# vca_core.net
KiCad netlist of a schematic drawn in Altium Designer
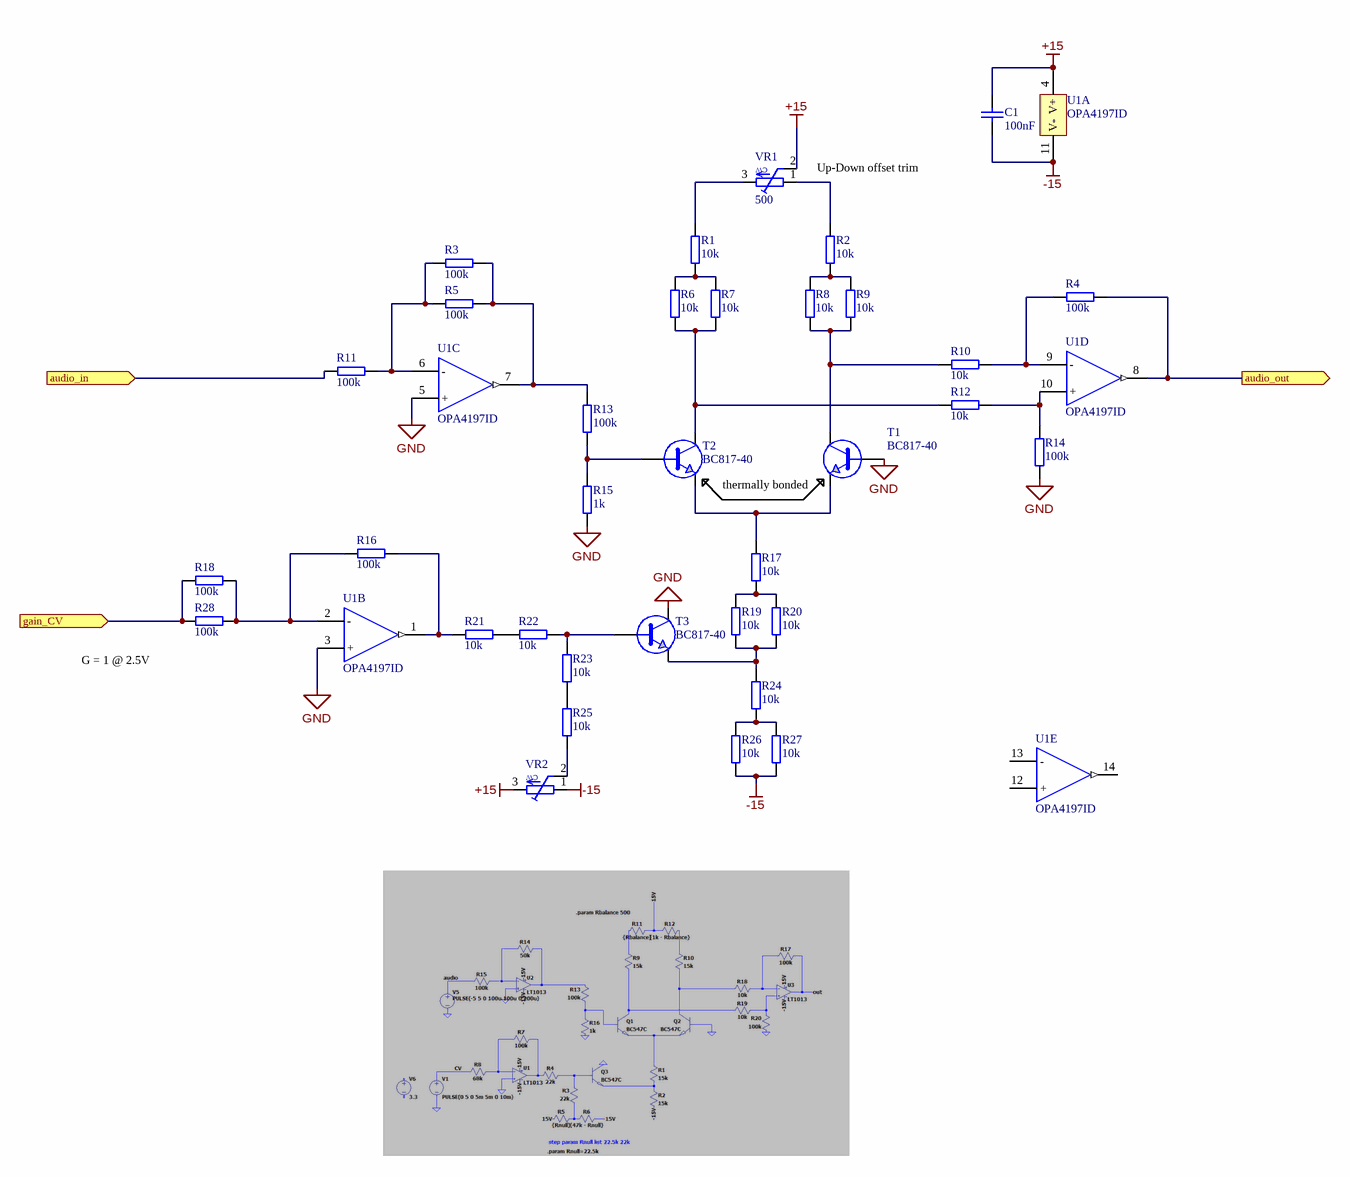
[diagram p0: vca_core.SchDoc]

(export (version "E")
  (design (tool "Eeschema 10.0.6"))
  (components
    (comp (ref "C1")
      (value "100nF")
      (footprint "WCAP-CSGP_0603_L1.6W0.8H0.8_Reflow")
      (description "WCAP-CSGP Multilayer Ceramic Chip Capacitor, General Purpose, size 0603, X7R, 100nF, 50V")
      (fields
        (field (name "MANUFACTURER") "Wurth Elektronik")
        (field (name "MANUFACTURER PART NUMBER") "885012206095")
      )
      (libsource (lib "Altium_WCAP-CSGP (rev22a)") (part "885012206095"))
    )
    (comp (ref "R1")
      (value "10k")
      (footprint "RESC1608X06N(SMR0603)")
      (description "Thick Film resistor, 0603 Size, universal value, 0.1 W")
      (libsource (lib "Kubikova integrovana knihovna ") (part "R 0603 universal"))
    )
    (comp (ref "R2")
      (value "10k")
      (footprint "RESC1608X06N(SMR0603)")
      (description "Thick Film resistor, 0603 Size, universal value, 0.1 W")
      (libsource (lib "Kubikova integrovana knihovna ") (part "R 0603 universal"))
    )
    (comp (ref "R3")
      (value "100k")
      (footprint "RESC1608X06N(SMR0603)")
      (description "Thick Film resistor, 0603 Size, universal value, 0.1 W")
      (libsource (lib "Kubikova integrovana knihovna ") (part "R 0603 universal"))
    )
    (comp (ref "R4")
      (value "100k")
      (footprint "RESC1608X06N(SMR0603)")
      (description "Thick Film resistor, 0603 Size, universal value, 0.1 W")
      (libsource (lib "Kubikova integrovana knihovna ") (part "R 0603 universal"))
    )
    (comp (ref "R5")
      (value "100k")
      (footprint "RESC1608X06N(SMR0603)")
      (description "Thick Film resistor, 0603 Size, universal value, 0.1 W")
      (libsource (lib "Kubikova integrovana knihovna ") (part "R 0603 universal"))
    )
    (comp (ref "R6")
      (value "10k")
      (footprint "RESC1608X06N(SMR0603)")
      (description "Thick Film resistor, 0603 Size, universal value, 0.1 W")
      (libsource (lib "Kubikova integrovana knihovna ") (part "R 0603 universal"))
    )
    (comp (ref "R7")
      (value "10k")
      (footprint "RESC1608X06N(SMR0603)")
      (description "Thick Film resistor, 0603 Size, universal value, 0.1 W")
      (libsource (lib "Kubikova integrovana knihovna ") (part "R 0603 universal"))
    )
    (comp (ref "R8")
      (value "10k")
      (footprint "RESC1608X06N(SMR0603)")
      (description "Thick Film resistor, 0603 Size, universal value, 0.1 W")
      (libsource (lib "Kubikova integrovana knihovna ") (part "R 0603 universal"))
    )
    (comp (ref "R9")
      (value "10k")
      (footprint "RESC1608X06N(SMR0603)")
      (description "Thick Film resistor, 0603 Size, universal value, 0.1 W")
      (libsource (lib "Kubikova integrovana knihovna ") (part "R 0603 universal"))
    )
    (comp (ref "R10")
      (value "10k")
      (footprint "RESC1608X06N(SMR0603)")
      (description "Thick Film resistor, 0603 Size, universal value, 0.1 W")
      (libsource (lib "Kubikova integrovana knihovna ") (part "R 0603 universal"))
    )
    (comp (ref "R11")
      (value "100k")
      (footprint "RESC1608X06N(SMR0603)")
      (description "Thick Film resistor, 0603 Size, universal value, 0.1 W")
      (libsource (lib "Kubikova integrovana knihovna ") (part "R 0603 universal"))
    )
    (comp (ref "R12")
      (value "10k")
      (footprint "RESC1608X06N(SMR0603)")
      (description "Thick Film resistor, 0603 Size, universal value, 0.1 W")
      (libsource (lib "Kubikova integrovana knihovna ") (part "R 0603 universal"))
    )
    (comp (ref "R13")
      (value "100k")
      (footprint "RESC1608X06N(SMR0603)")
      (description "Thick Film resistor, 0603 Size, universal value, 0.1 W")
      (libsource (lib "Kubikova integrovana knihovna ") (part "R 0603 universal"))
    )
    (comp (ref "R14")
      (value "100k")
      (footprint "RESC1608X06N(SMR0603)")
      (description "Thick Film resistor, 0603 Size, universal value, 0.1 W")
      (libsource (lib "Kubikova integrovana knihovna ") (part "R 0603 universal"))
    )
    (comp (ref "R15")
      (value "1k")
      (footprint "RESC1608X06N(SMR0603)")
      (description "Thick Film resistor, 0603 Size, universal value, 0.1 W")
      (libsource (lib "Kubikova integrovana knihovna ") (part "R 0603 universal"))
    )
    (comp (ref "R16")
      (value "100k")
      (footprint "RESC1608X06N(SMR0603)")
      (description "Thick Film resistor, 0603 Size, universal value, 0.1 W")
      (libsource (lib "Kubikova integrovana knihovna ") (part "R 0603 universal"))
    )
    (comp (ref "R17")
      (value "10k")
      (footprint "RESC1608X06N(SMR0603)")
      (description "Thick Film resistor, 0603 Size, universal value, 0.1 W")
      (libsource (lib "Kubikova integrovana knihovna ") (part "R 0603 universal"))
    )
    (comp (ref "R18")
      (value "100k")
      (footprint "RESC1608X06N(SMR0603)")
      (description "Thick Film resistor, 0603 Size, universal value, 0.1 W")
      (libsource (lib "Kubikova integrovana knihovna ") (part "R 0603 universal"))
    )
    (comp (ref "R19")
      (value "10k")
      (footprint "RESC1608X06N(SMR0603)")
      (description "Thick Film resistor, 0603 Size, universal value, 0.1 W")
      (libsource (lib "Kubikova integrovana knihovna ") (part "R 0603 universal"))
    )
    (comp (ref "R20")
      (value "10k")
      (footprint "RESC1608X06N(SMR0603)")
      (description "Thick Film resistor, 0603 Size, universal value, 0.1 W")
      (libsource (lib "Kubikova integrovana knihovna ") (part "R 0603 universal"))
    )
    (comp (ref "R21")
      (value "10k")
      (footprint "RESC1608X06N(SMR0603)")
      (description "Thick Film resistor, 0603 Size, universal value, 0.1 W")
      (libsource (lib "Kubikova integrovana knihovna ") (part "R 0603 universal"))
    )
    (comp (ref "R22")
      (value "10k")
      (footprint "RESC1608X06N(SMR0603)")
      (description "Thick Film resistor, 0603 Size, universal value, 0.1 W")
      (libsource (lib "Kubikova integrovana knihovna ") (part "R 0603 universal"))
    )
    (comp (ref "R23")
      (value "10k")
      (footprint "RESC1608X06N(SMR0603)")
      (description "Thick Film resistor, 0603 Size, universal value, 0.1 W")
      (libsource (lib "Kubikova integrovana knihovna ") (part "R 0603 universal"))
    )
    (comp (ref "R24")
      (value "10k")
      (footprint "RESC1608X06N(SMR0603)")
      (description "Thick Film resistor, 0603 Size, universal value, 0.1 W")
      (libsource (lib "Kubikova integrovana knihovna ") (part "R 0603 universal"))
    )
    (comp (ref "R25")
      (value "10k")
      (footprint "RESC1608X06N(SMR0603)")
      (description "Thick Film resistor, 0603 Size, universal value, 0.1 W")
      (libsource (lib "Kubikova integrovana knihovna ") (part "R 0603 universal"))
    )
    (comp (ref "R26")
      (value "10k")
      (footprint "RESC1608X06N(SMR0603)")
      (description "Thick Film resistor, 0603 Size, universal value, 0.1 W")
      (libsource (lib "Kubikova integrovana knihovna ") (part "R 0603 universal"))
    )
    (comp (ref "R27")
      (value "10k")
      (footprint "RESC1608X06N(SMR0603)")
      (description "Thick Film resistor, 0603 Size, universal value, 0.1 W")
      (libsource (lib "Kubikova integrovana knihovna ") (part "R 0603 universal"))
    )
    (comp (ref "R28")
      (value "100k")
      (footprint "RESC1608X06N(SMR0603)")
      (description "Thick Film resistor, 0603 Size, universal value, 0.1 W")
      (libsource (lib "Kubikova integrovana knihovna ") (part "R 0603 universal"))
    )
    (comp (ref "T1")
      (value "BC817-40")
      (footprint "SOT95P230X110-3N(SOT23)")
      (description "SSw; NPN; ??Ohm; 45V; 0.5A; 1x;")
      (libsource (lib "altium_sql") (part "NPN_BEC"))
    )
    (comp (ref "T2")
      (value "BC817-40")
      (footprint "SOT95P230X110-3N(SOT23)")
      (description "SSw; NPN; ??Ohm; 45V; 0.5A; 1x;")
      (libsource (lib "altium_sql") (part "NPN_BEC"))
    )
    (comp (ref "T3")
      (value "BC817-40")
      (footprint "SOT95P230X110-3N(SOT23)")
      (description "SSw; NPN; ??Ohm; 45V; 0.5A; 1x;")
      (libsource (lib "altium_sql") (part "NPN_BEC"))
    )
    (comp (ref "U1")
      (value "OPA4197ID")
      (footprint "SOIC127P600X175-14N(SO-14)")
      (description "IC; Opamp; 4.5V; 36V; 4x;")
      (fields (field (name "MANUFACTURER") "Texas Instruments: OPA4197IDR"))
      (libsource (lib "altium_sql") (part "OP_AMP_QUAD_1"))
    )
    (comp (ref "VR1")
      (value "500")
      (footprint "64W")
      (description "093 - 3/8\" Square (10 mm) Multi-Turn Cermet Trimmer")
      (libsource (lib "Kubikova integrovana knihovna ") (part "Trimmer universal 3/8 (10mm)"))
    )
    (comp (ref "VR2")
      (value "~")
      (footprint "64W")
      (description "093 - 3/8\" Square (10 mm) Multi-Turn Cermet Trimmer")
      (libsource (lib "Kubikova integrovana knihovna ") (part "Trimmer universal 3/8 (10mm)"))
    )
  )
  (nets
    (net (code "1") (name "+15") (class "Default")
      (node (ref "C1") (pin "2") (pinfunction "2_2") (pintype "passive"))
      (node (ref "U1") (pin "4") (pinfunction "V+_4") (pintype "power_in"))
      (node (ref "VR1") (pin "2") (pinfunction "2_2") (pintype "passive"))
      (node (ref "VR2") (pin "3") (pinfunction "3_3") (pintype "passive"))
    )
    (net (code "2") (name "-15") (class "Default")
      (node (ref "C1") (pin "1") (pinfunction "1_1") (pintype "passive"))
      (node (ref "R26") (pin "2") (pinfunction "2_2") (pintype "passive"))
      (node (ref "R27") (pin "2") (pinfunction "2_2") (pintype "passive"))
      (node (ref "U1") (pin "11") (pinfunction "V-_11") (pintype "power_in"))
      (node (ref "VR2") (pin "1") (pinfunction "1_1") (pintype "passive"))
    )
    (net (code "3") (name "/audio_in") (class "Default")
      (node (ref "R11") (pin "1") (pinfunction "1_1") (pintype "passive"))
    )
    (net (code "4") (name "/audio_out") (class "Default")
      (node (ref "R4") (pin "1") (pinfunction "1_1") (pintype "passive"))
      (node (ref "U1") (pin "8") (pinfunction "OUT3_8") (pintype "output"))
    )
    (net (code "5") (name "/gain_CV") (class "Default")
      (node (ref "R18") (pin "2") (pinfunction "2_2") (pintype "passive"))
      (node (ref "R28") (pin "2") (pinfunction "2_2") (pintype "passive"))
    )
    (net (code "6") (name "GND") (class "Default")
      (node (ref "R14") (pin "1") (pinfunction "1_1") (pintype "passive"))
      (node (ref "R15") (pin "2") (pinfunction "2_2") (pintype "passive"))
      (node (ref "T1") (pin "1") (pinfunction "B_1") (pintype "passive"))
      (node (ref "T3") (pin "3") (pinfunction "C_3") (pintype "passive"))
      (node (ref "U1") (pin "3") (pinfunction "+_3") (pintype "passive"))
      (node (ref "U1") (pin "5") (pinfunction "+_5") (pintype "passive"))
    )
    (net (code "7") (name "Net-(R1-Pad1)") (class "Default")
      (node (ref "R1") (pin "1") (pinfunction "1_1") (pintype "passive"))
      (node (ref "VR1") (pin "3") (pinfunction "3_3") (pintype "passive"))
    )
    (net (code "8") (name "Net-(R1-Pad2)") (class "Default")
      (node (ref "R1") (pin "2") (pinfunction "2_2") (pintype "passive"))
      (node (ref "R6") (pin "1") (pinfunction "1_1") (pintype "passive"))
      (node (ref "R7") (pin "1") (pinfunction "1_1") (pintype "passive"))
    )
    (net (code "9") (name "Net-(R2-Pad1)") (class "Default")
      (node (ref "R2") (pin "1") (pinfunction "1_1") (pintype "passive"))
      (node (ref "VR1") (pin "1") (pinfunction "1_1") (pintype "passive"))
    )
    (net (code "10") (name "Net-(R2-Pad2)") (class "Default")
      (node (ref "R2") (pin "2") (pinfunction "2_2") (pintype "passive"))
      (node (ref "R8") (pin "1") (pinfunction "1_1") (pintype "passive"))
      (node (ref "R9") (pin "1") (pinfunction "1_1") (pintype "passive"))
    )
    (net (code "11") (name "Net-(R17-Pad2)") (class "Default")
      (node (ref "R17") (pin "2") (pinfunction "2_2") (pintype "passive"))
      (node (ref "R19") (pin "1") (pinfunction "1_1") (pintype "passive"))
      (node (ref "R20") (pin "1") (pinfunction "1_1") (pintype "passive"))
    )
    (net (code "12") (name "Net-(R21-Pad2)") (class "Default")
      (node (ref "R21") (pin "2") (pinfunction "2_2") (pintype "passive"))
      (node (ref "R22") (pin "1") (pinfunction "1_1") (pintype "passive"))
    )
    (net (code "13") (name "Net-(R23-Pad2)") (class "Default")
      (node (ref "R23") (pin "2") (pinfunction "2_2") (pintype "passive"))
      (node (ref "R25") (pin "1") (pinfunction "1_1") (pintype "passive"))
    )
    (net (code "14") (name "Net-(R24-Pad2)") (class "Default")
      (node (ref "R24") (pin "2") (pinfunction "2_2") (pintype "passive"))
      (node (ref "R26") (pin "1") (pinfunction "1_1") (pintype "passive"))
      (node (ref "R27") (pin "1") (pinfunction "1_1") (pintype "passive"))
    )
    (net (code "15") (name "Net-(R25-Pad2)") (class "Default")
      (node (ref "R25") (pin "2") (pinfunction "2_2") (pintype "passive"))
      (node (ref "VR2") (pin "2") (pinfunction "2_2") (pintype "passive"))
    )
    (net (code "16") (name "Net-(T1-C)") (class "Default")
      (node (ref "R10") (pin "2") (pinfunction "2_2") (pintype "passive"))
      (node (ref "R8") (pin "2") (pinfunction "2_2") (pintype "passive"))
      (node (ref "R9") (pin "2") (pinfunction "2_2") (pintype "passive"))
      (node (ref "T1") (pin "3") (pinfunction "C_3") (pintype "passive"))
    )
    (net (code "17") (name "Net-(T1-E)") (class "Default")
      (node (ref "R17") (pin "1") (pinfunction "1_1") (pintype "passive"))
      (node (ref "T1") (pin "2") (pinfunction "E_2") (pintype "passive"))
      (node (ref "T2") (pin "2") (pinfunction "E_2") (pintype "passive"))
    )
    (net (code "18") (name "Net-(T2-B)") (class "Default")
      (node (ref "R13") (pin "2") (pinfunction "2_2") (pintype "passive"))
      (node (ref "R15") (pin "1") (pinfunction "1_1") (pintype "passive"))
      (node (ref "T2") (pin "1") (pinfunction "B_1") (pintype "passive"))
    )
    (net (code "19") (name "Net-(T2-C)") (class "Default")
      (node (ref "R12") (pin "2") (pinfunction "2_2") (pintype "passive"))
      (node (ref "R6") (pin "2") (pinfunction "2_2") (pintype "passive"))
      (node (ref "R7") (pin "2") (pinfunction "2_2") (pintype "passive"))
      (node (ref "T2") (pin "3") (pinfunction "C_3") (pintype "passive"))
    )
    (net (code "20") (name "Net-(T3-B)") (class "Default")
      (node (ref "R22") (pin "2") (pinfunction "2_2") (pintype "passive"))
      (node (ref "R23") (pin "1") (pinfunction "1_1") (pintype "passive"))
      (node (ref "T3") (pin "1") (pinfunction "B_1") (pintype "passive"))
    )
    (net (code "21") (name "Net-(T3-E)") (class "Default")
      (node (ref "R19") (pin "2") (pinfunction "2_2") (pintype "passive"))
      (node (ref "R20") (pin "2") (pinfunction "2_2") (pintype "passive"))
      (node (ref "R24") (pin "1") (pinfunction "1_1") (pintype "passive"))
      (node (ref "T3") (pin "2") (pinfunction "E_2") (pintype "passive"))
    )
    (net (code "22") (name "Net-(U1B--)") (class "Default")
      (node (ref "R16") (pin "2") (pinfunction "2_2") (pintype "passive"))
      (node (ref "R18") (pin "1") (pinfunction "1_1") (pintype "passive"))
      (node (ref "R28") (pin "1") (pinfunction "1_1") (pintype "passive"))
      (node (ref "U1") (pin "2") (pinfunction "-_2") (pintype "passive"))
    )
    (net (code "23") (name "Net-(U1B-OUT1)") (class "Default")
      (node (ref "R16") (pin "1") (pinfunction "1_1") (pintype "passive"))
      (node (ref "R21") (pin "1") (pinfunction "1_1") (pintype "passive"))
      (node (ref "U1") (pin "1") (pinfunction "OUT1_1") (pintype "output"))
    )
    (net (code "24") (name "Net-(U1C--)") (class "Default")
      (node (ref "R11") (pin "2") (pinfunction "2_2") (pintype "passive"))
      (node (ref "R3") (pin "1") (pinfunction "1_1") (pintype "passive"))
      (node (ref "R5") (pin "1") (pinfunction "1_1") (pintype "passive"))
      (node (ref "U1") (pin "6") (pinfunction "-_6") (pintype "passive"))
    )
    (net (code "25") (name "Net-(U1C-OUT2)") (class "Default")
      (node (ref "R13") (pin "1") (pinfunction "1_1") (pintype "passive"))
      (node (ref "R3") (pin "2") (pinfunction "2_2") (pintype "passive"))
      (node (ref "R5") (pin "2") (pinfunction "2_2") (pintype "passive"))
      (node (ref "U1") (pin "7") (pinfunction "OUT2_7") (pintype "output"))
    )
    (net (code "26") (name "Net-(U1D-+)") (class "Default")
      (node (ref "R12") (pin "1") (pinfunction "1_1") (pintype "passive"))
      (node (ref "R14") (pin "2") (pinfunction "2_2") (pintype "passive"))
      (node (ref "U1") (pin "10") (pinfunction "+_10") (pintype "passive"))
    )
    (net (code "27") (name "Net-(U1D--)") (class "Default")
      (node (ref "R10") (pin "1") (pinfunction "1_1") (pintype "passive"))
      (node (ref "R4") (pin "2") (pinfunction "2_2") (pintype "passive"))
      (node (ref "U1") (pin "9") (pinfunction "-_9") (pintype "passive"))
    )
    (net (code "28") (name "unconnected-(U1E-+-Pad12)") (class "Default")
      (node (ref "U1") (pin "12") (pinfunction "+_12") (pintype "passive"))
    )
    (net (code "29") (name "unconnected-(U1E---Pad13)") (class "Default")
      (node (ref "U1") (pin "13") (pinfunction "-_13") (pintype "passive"))
    )
    (net (code "30") (name "unconnected-(U1E-OUT4-Pad14)") (class "Default")
      (node (ref "U1") (pin "14") (pinfunction "OUT4_14") (pintype "output"))
    )
  )
)
